# JacDacMicroBitShieldLP_29.net
KiCad netlist of a schematic drawn in Altium Designer
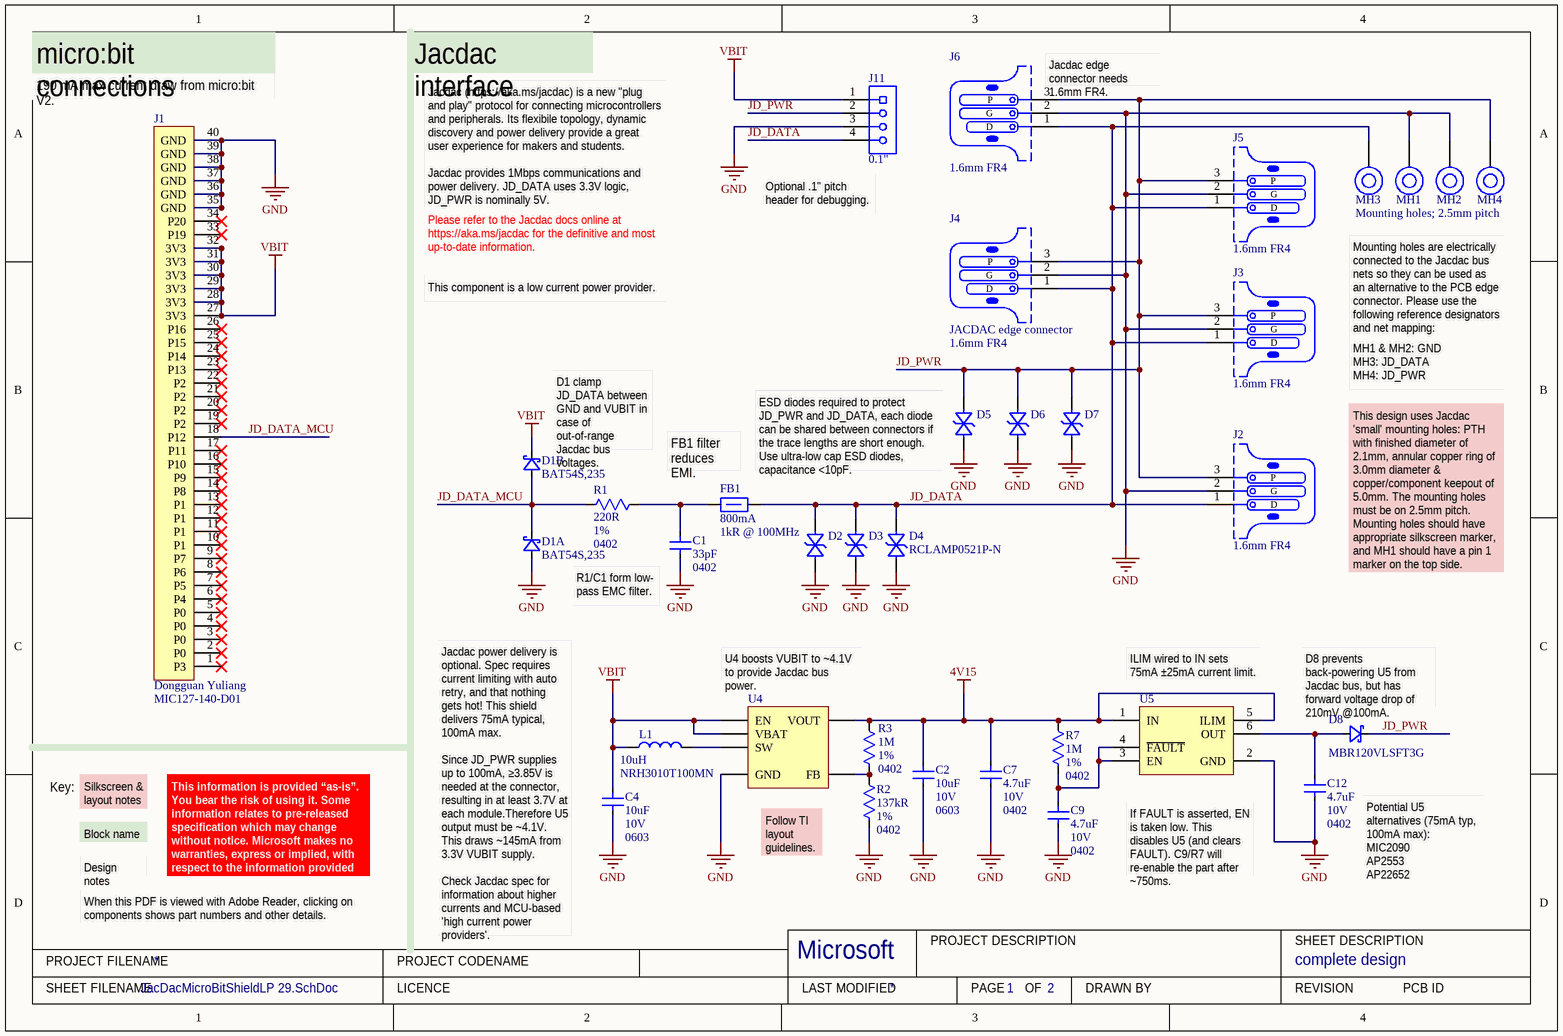
[diagram p0: JacDacMicroBitShieldLP 29.SchDoc]

(export (version "E")
  (design (tool "Eeschema 10.0.6"))
  (components
    (comp (ref "C1")
      (value "CL05C330JB51PNC")
      (footprint "C0402_0.55MM - without outline")
      (description "CAP CER 33PF 50V NP0 0402")
      (fields
        (field (name "MANUFACTURER") "Samsung")
        (field (name "TOLERANCE") "5%")
        (field (name "CAPACITANCE") "33pF")
        (field (name "CASE CODE (IMPERIAL)") "0402")
        (field (name "CHECKED") "?")
        (field (name "CREATED") "DG")
      )
      (libsource (lib "Samsung") (part "CL05C330JB51PNC"))
    )
    (comp (ref "C2")
      (value "CL10A106KP8NNNC")
      (footprint "C0603 - without outline")
      (description "CAP CER 10UF 10V X5R 0603")
      (fields
        (field (name "MANUFACTURER") "Samsung")
        (field (name "TOLERANCE") "10%")
        (field (name "CAPACITANCE") "10uF")
        (field (name "VOLTAGE RATING") "10V")
        (field (name "CASE CODE (IMPERIAL)") "0603")
      )
      (libsource (lib "Samsung") (part "CL10A106KP8NNNC"))
    )
    (comp (ref "C4")
      (value "CL10A106KP8NNNC")
      (footprint "C0603 - without outline")
      (description "CAP CER 10UF 10V X5R 0603")
      (fields
        (field (name "MANUFACTURER") "Samsung")
        (field (name "TOLERANCE") "10%")
        (field (name "CAPACITANCE") "10uF")
        (field (name "VOLTAGE RATING") "10V")
        (field (name "CASE CODE (IMPERIAL)") "0603")
      )
      (libsource (lib "Samsung") (part "CL10A106KP8NNNC"))
    )
    (comp (ref "C7")
      (value "CL05A475MP5NRNC")
      (footprint "R0402 - Without outline")
      (description "CAP CER 4.7UF 10V X5R 0402")
      (fields
        (field (name "MANUFACTURER") "Samsung")
        (field (name "TOLERANCE") "20%")
        (field (name "CAPACITANCE") "4.7uF")
        (field (name "VOLTAGE RATING") "10V")
        (field (name "CASE CODE (IMPERIAL)") "0402")
        (field (name "CREATED BY") "D. Gakure")
        (field (name "CHECKED BY") "?")
      )
      (libsource (lib "Samsung") (part "CL05A475MP5NRNC"))
    )
    (comp (ref "C9")
      (value "CL05A475MP5NRNC")
      (footprint "R0402 - Without outline")
      (description "CAP CER 4.7UF 10V X5R 0402")
      (fields
        (field (name "MANUFACTURER") "Samsung")
        (field (name "TOLERANCE") "20%")
        (field (name "CAPACITANCE") "4.7uF")
        (field (name "VOLTAGE RATING") "10V")
        (field (name "CASE CODE (IMPERIAL)") "0402")
        (field (name "CREATED BY") "D. Gakure")
        (field (name "CHECKED BY") "?")
      )
      (libsource (lib "Samsung") (part "CL05A475MP5NRNC"))
    )
    (comp (ref "C12")
      (value "CL05A475MP5NRNC")
      (footprint "R0402 - Without outline")
      (description "CAP CER 4.7UF 10V X5R 0402")
      (fields
        (field (name "MANUFACTURER") "Samsung")
        (field (name "TOLERANCE") "20%")
        (field (name "CAPACITANCE") "4.7uF")
        (field (name "VOLTAGE RATING") "10V")
        (field (name "CASE CODE (IMPERIAL)") "0402")
        (field (name "CREATED BY") "D. Gakure")
        (field (name "CHECKED BY") "?")
      )
      (libsource (lib "Samsung") (part "CL05A475MP5NRNC"))
    )
    (comp (ref "D1")
      (value "BAT54S")
      (footprint "NXP-BAT54S-TO-236AB - without outline")
      (description "DIODE ARRAY SCHOTTKY 30V SOT23")
      (fields (field (name "MANUFACTURER") "Nexperia") (field (name "MANUFACTURER PART NUMBER") "BAT54S,235"))
      (libsource (lib "NXP") (part "BAT54S"))
    )
    (comp (ref "D2")
      (value "RCLAMP0521P-N")
      (footprint "TVS 0402 - L")
      (description "Bidirectional 5V (Max) 6V 16V 3.5A (8/20us) 0402 TVS RoHS")
      (fields
        (field (name "MANUFACTURER") "Born Semiconductor")
        (field (name "CREATED BY") "D Gakure")
        (field (name "CHECKED BY") "?")
      )
      (libsource (lib "BornSemiconductor") (part "RCLAMP0521P-N"))
    )
    (comp (ref "D3")
      (value "RCLAMP0521P-N")
      (footprint "TVS 0402 - L")
      (description "Bidirectional 5V (Max) 6V 16V 3.5A (8/20us) 0402 TVS RoHS")
      (fields
        (field (name "MANUFACTURER") "Born Semiconductor")
        (field (name "CREATED BY") "D Gakure")
        (field (name "CHECKED BY") "?")
      )
      (libsource (lib "BornSemiconductor") (part "RCLAMP0521P-N"))
    )
    (comp (ref "D4")
      (value "RCLAMP0521P-N")
      (footprint "TVS 0402 - L")
      (description "Bidirectional 5V (Max) 6V 16V 3.5A (8/20us) 0402 TVS RoHS")
      (fields
        (field (name "MANUFACTURER") "Born Semiconductor")
        (field (name "MANUFACTURER PART NUMBER") "RCLAMP0521P-N")
        (field (name "CREATED BY") "D Gakure")
        (field (name "CHECKED BY") "?")
      )
      (libsource (lib "BornSemiconductor") (part "RCLAMP0521P-N"))
    )
    (comp (ref "D5")
      (value "RCLAMP0521P-N")
      (footprint "TVS 0402 - L")
      (description "Bidirectional 5V (Max) 6V 16V 3.5A (8/20us) 0402 TVS RoHS")
      (fields
        (field (name "MANUFACTURER") "Born Semiconductor")
        (field (name "CREATED BY") "D Gakure")
        (field (name "CHECKED BY") "?")
      )
      (libsource (lib "BornSemiconductor") (part "RCLAMP0521P-N"))
    )
    (comp (ref "D6")
      (value "RCLAMP0521P-N")
      (footprint "TVS 0402 - L")
      (description "Bidirectional 5V (Max) 6V 16V 3.5A (8/20us) 0402 TVS RoHS")
      (fields
        (field (name "MANUFACTURER") "Born Semiconductor")
        (field (name "CREATED BY") "D Gakure")
        (field (name "CHECKED BY") "?")
      )
      (libsource (lib "BornSemiconductor") (part "RCLAMP0521P-N"))
    )
    (comp (ref "D7")
      (value "RCLAMP0521P-N")
      (footprint "TVS 0402 - L")
      (description "Bidirectional 5V (Max) 6V 16V 3.5A (8/20us) 0402 TVS RoHS")
      (fields
        (field (name "MANUFACTURER") "Born Semiconductor")
        (field (name "CREATED BY") "D Gakure")
        (field (name "CHECKED BY") "?")
      )
      (libsource (lib "BornSemiconductor") (part "RCLAMP0521P-N"))
    )
    (comp (ref "D8")
      (value "MBR120VLSFT3G")
      (footprint "MBR120VLSFT3G")
      (description "DIODE SCHOTTKY 20V 1A SOD123FL")
      (fields
        (field (name "MANUFACTURER") "ON Semiconductor")
        (field (name "MANUFACTURER PART NUMBER") "MBR120VLSFT3G")
      )
      (libsource (lib "OnSemiconductor") (part "MBR120VLSFT3G"))
    )
    (comp (ref "FB1")
      (value "TDK MPZ1608S102ATA00")
      (footprint "TDK MPZ1608 0.8mm - without outline")
      (description "0603 1k@100MHz 0.8A chip")
      (fields
        (field (name "TOLERANCE") "25%")
        (field (name "MANUFACTURER") "TDK")
        (field (name "CURRENT RATING") "800mA")
        (field (name "IMPEDANCE") "1kR @ 100MHz")
      )
      (libsource (lib "TDK") (part "TDK MPZ1608S102ATA00"))
    )
    (comp (ref "J1")
      (value "Planar 1x40p 1.27 mm pitch edge connector for the micro:bit")
      (footprint "MIC127-140-D01")
      (description "\"Same plane\" 1x40p 1.27mm Dongguan Yuliang BBC micro:bit edge connector")
      (fields
        (field (name "MANUFACTURER") "Dongguan Yuliang")
        (field (name "MANUFACTURER PART NUMBER") "MIC127-140-D01")
      )
      (libsource (lib "Yuliang") (part "MIC127-140-D01"))
    )
    (comp (ref "J2")
      (value "Jacdac edge connector")
      (footprint "JACDAC_edge_connector:JACDAC_EDGE_CONNECTOR_NO_TRACES")
      (description "3 pin jacdac edge connector 1.27mm pitch")
      (fields
        (field (name "MANUFACTURER PART NUMBER") "JACDAC_EDGE_CONNECTOR")
        (field (name "PCB TYPE") "1.6mm FR4")
        (field (name "CHECKED BY") "?")
        (field (name "CREATED BY") "D. Gakure")
      )
      (libsource (lib "generic-con") (part "Jacdac edge connector"))
    )
    (comp (ref "J3")
      (value "Jacdac edge connector")
      (footprint "JACDAC_edge_connector:JACDAC_EDGE_CONNECTOR_NO_TRACES")
      (description "3 pin jacdac edge connector 1.27mm pitch")
      (fields
        (field (name "MANUFACTURER PART NUMBER") "JACDAC_EDGE_CONNECTOR")
        (field (name "PCB TYPE") "1.6mm FR4")
        (field (name "CHECKED BY") "?")
        (field (name "CREATED BY") "D. Gakure")
      )
      (libsource (lib "generic-con") (part "Jacdac edge connector"))
    )
    (comp (ref "J4")
      (value "JACDAC edge connector")
      (footprint "JACDAC_edge_connector:JACDAC_EDGE_CONNECTOR_NO_TRACES")
      (description "3 pin jacdac edge connector 1.27mm pitch")
      (fields
        (field (name "MANUFACTURER PART NUMBER") "JACDAC_EDGE_CONNECTOR")
        (field (name "PCB TYPE") "1.6mm FR4")
        (field (name "CHECKED BY") "?")
        (field (name "CREATED BY") "D. Gakure")
      )
      (libsource (lib "") (part "Jacdac edge connector_1"))
    )
    (comp (ref "J5")
      (value "Jacdac edge connector")
      (footprint "JACDAC_edge_connector:JACDAC_EDGE_CONNECTOR_NO_TRACES")
      (description "3 pin jacdac edge connector 1.27mm pitch")
      (fields
        (field (name "MANUFACTURER PART NUMBER") "JACDAC_EDGE_CONNECTOR")
        (field (name "PCB TYPE") "1.6mm FR4")
        (field (name "CHECKED BY") "?")
        (field (name "CREATED BY") "D. Gakure")
      )
      (libsource (lib "generic-con") (part "Jacdac edge connector"))
    )
    (comp (ref "J6")
      (value "Jacdac edge connector")
      (footprint "JACDAC_edge_connector:JACDAC_EDGE_CONNECTOR_NO_TRACES")
      (description "3 pin jacdac edge connector 1.27mm pitch")
      (fields
        (field (name "MANUFACTURER PART NUMBER") "JACDAC_EDGE_CONNECTOR")
        (field (name "PCB TYPE") "1.6mm FR4")
        (field (name "CHECKED BY") "?")
        (field (name "CREATED BY") "D. Gakure")
      )
      (libsource (lib "") (part "Jacdac edge connector_1"))
    )
    (comp (ref "J11")
      (value "0.1\"")
      (footprint "Generic 1x4 2.54mm header")
      (description "2.54mm, 4x1 way, vertical, square pin, gold plate")
      (fields
        (field (name "MANUFACTURER") "Multicomp")
        (field (name "MANUFACTURER PART NUMBER") "2211S-04G")
        (field (name "CREATED BY") "HUGHWI")
      )
      (libsource (lib "generic-con") (part "Header Multicomp 2211S-04G-whitesch"))
    )
    (comp (ref "L1")
      (value "NRH3010T100MN")
      (footprint "NRH3010T100MN")
      (fields
        (field (name "TOLERANCE") "20%")
        (field (name "INDUCTANCE") "10uH")
        (field (name "MANUFACTURER") "Taiyo Yuden")
        (field (name "MANUFACTURER PART NUMBER") "NRH3010T100MN")
      )
      (libsource (lib "TaiyoYuden ") (part "NRH3010T100MN"))
    )
    (comp (ref "MH1")
      (value "~")
      (footprint "MH_5.0MMK_3.0MMC_2.1MMD_PTH:MH_5.0MMK_3.0MMC_2.1MMD_PTH")
      (description "Mounting Hole 5.0mm keepout, 3.0mm annualar ring and 2.1mm Drill PTH")
      (libsource (lib "generic") (part "MH_5.0MMK_3.0MMC_2.1MMD_PTH"))
    )
    (comp (ref "MH2")
      (value "Mounting holes; 2.5 mm pitch")
      (footprint "MH_5.0MMK_3.0MMC_2.1MMD_PTH:MH_5.0MMK_3.0MMC_2.1MMD_PTH")
      (description "Mounting Hole 5.0mm keepout, 3.0mm annualar ring and 2.1mm Drill PTH")
      (libsource (lib "generic") (part "MH_5.0MMK_3.0MMC_2.1MMD_PTH"))
    )
    (comp (ref "MH3")
      (value "Mounting holes; 2.5mm pitch")
      (footprint "MH_5.0MMK_3.0MMC_2.1MMD_PTH:MH_5.0MMK_3.0MMC_2.1MMD_PTH")
      (description "Mounting Hole 5.0mm keepout, 3.0mm annualar ring and 2.1mm Drill PTH")
      (libsource (lib "generic") (part "MH_5.0MMK_3.0MMC_2.1MMD_PTH"))
    )
    (comp (ref "MH4")
      (value "MH_5.0MMK_3.0MMC_2.1MMD_PTH")
      (footprint "MH_5.0MMK_3.0MMC_2.1MMD_PTH:MH_5.0MMK_3.0MMC_2.1MMD_PTH")
      (description "Mounting Hole 5.0mm keepout, 3.0mm annualar ring and 2.1mm Drill PTH")
      (libsource (lib "generic") (part "MH_5.0MMK_3.0MMC_2.1MMD_PTH"))
    )
    (comp (ref "R1")
      (value "0402WGF2200TCE")
      (footprint "UNIROYAL-0402:R0402 - Without outline")
      (description "RES SMD 220 OHM 1% 1/16W 0402")
      (fields
        (field (name "MANUFACTURER") "Uniroyal Elec")
        (field (name "RESISTANCE") "220R")
        (field (name "TOLERANCE") "1%")
        (field (name "CASE CODE (IMPERIAL)") "0402")
      )
      (libsource (lib "UniroyalElec") (part "0402WGF2200TCE"))
    )
    (comp (ref "R2")
      (value "RC0402FR-07137KL")
      (footprint "R0402 - Without outline")
      (description "RES SMD 137K OHM 1% 1/16W 0402")
      (fields
        (field (name "MANUFACTURER") "Yageo")
        (field (name "RESISTANCE") "137kR")
        (field (name "TOLERANCE") "1%")
        (field (name "CASE CODE (IMPERIAL)") "0402")
      )
      (libsource (lib "Yageo") (part "RC0402FR-07137KL"))
    )
    (comp (ref "R3")
      (value "0402WGF1004TCE")
      (footprint "UNIROYAL-0402:R0402 - Without outline")
      (description "RES SMD 1M OHM 1% 1/16W 0402")
      (fields
        (field (name "MANUFACTURER") "Uniroyal Elec")
        (field (name "RESISTANCE") "1M")
        (field (name "TOLERANCE") "1%")
        (field (name "CASE CODE (IMPERIAL)") "0402")
      )
      (libsource (lib "UniroyalElec") (part "0402WGF1004TCE"))
    )
    (comp (ref "R7")
      (value "0402WGF1004TCE")
      (footprint "UNIROYAL-0402:R0402 - Without outline")
      (description "RES SMD 1M OHM 1% 1/16W 0402")
      (fields
        (field (name "MANUFACTURER") "Uniroyal Elec")
        (field (name "RESISTANCE") "1M")
        (field (name "TOLERANCE") "1%")
        (field (name "CASE CODE (IMPERIAL)") "0402")
      )
      (libsource (lib "UniroyalElec") (part "0402WGF1004TCE"))
    )
    (comp (ref "U4")
      (value "TLV61220")
      (footprint "TI-TLV61220 - without_outline")
      (description "IC REG BST ADJ 0.22A SYNC SOT23")
      (fields (field (name "MANUFACTURER PART NUMBER") "TLV61220DBVR"))
      (libsource (lib "TexasInstruments") (part "TLV61220"))
    )
    (comp (ref "U5")
      (value "TPS2553DBVR")
      (footprint "TI-TPS2553 - without_outline")
      (libsource (lib "TexasInstruments") (part "TPS2553DBVR"))
    )
  )
  (nets
    (net (code "1") (name "/JD_DATA") (class "Default")
      (node (ref "D2") (pin "1") (pinfunction "K_1") (pintype "passive"))
      (node (ref "D3") (pin "1") (pinfunction "K_1") (pintype "passive"))
      (node (ref "D4") (pin "1") (pinfunction "K_1") (pintype "passive"))
      (node (ref "FB1") (pin "1") (pinfunction "1_1") (pintype "passive"))
      (node (ref "J11") (pin "4") (pinfunction "4_4") (pintype "passive"))
      (node (ref "J2") (pin "1") (pinfunction "D_1") (pintype "passive"))
      (node (ref "J3") (pin "1") (pinfunction "D_1") (pintype "passive"))
      (node (ref "J4") (pin "1") (pinfunction "D_1") (pintype "passive"))
      (node (ref "J5") (pin "1") (pinfunction "D_1") (pintype "passive"))
      (node (ref "J6") (pin "1") (pinfunction "D_1") (pintype "passive"))
      (node (ref "MH3") (pin "1") (pinfunction "1_1") (pintype "passive"))
    )
    (net (code "2") (name "/JD_DATA_MCU") (class "Default")
      (node (ref "D1") (pin "3") (pinfunction "K_3") (pintype "passive"))
      (node (ref "J1") (pin "18") (pinfunction "P12_18") (pintype "passive"))
      (node (ref "R1") (pin "1") (pinfunction "1_1") (pintype "passive"))
    )
    (net (code "3") (name "/JD_PWR") (class "Default")
      (node (ref "D5") (pin "1") (pinfunction "K_1") (pintype "passive"))
      (node (ref "D6") (pin "1") (pinfunction "K_1") (pintype "passive"))
      (node (ref "D7") (pin "1") (pinfunction "K_1") (pintype "passive"))
      (node (ref "D8") (pin "1") (pinfunction "K_1") (pintype "passive"))
      (node (ref "J11") (pin "2") (pinfunction "2_2") (pintype "passive"))
      (node (ref "J2") (pin "3") (pinfunction "P_3") (pintype "passive"))
      (node (ref "J3") (pin "3") (pinfunction "P_3") (pintype "passive"))
      (node (ref "J4") (pin "3") (pinfunction "P_3") (pintype "passive"))
      (node (ref "J5") (pin "3") (pinfunction "P_3") (pintype "passive"))
      (node (ref "J6") (pin "3") (pinfunction "P_3") (pintype "passive"))
      (node (ref "MH4") (pin "1") (pinfunction "1_1") (pintype "passive"))
    )
    (net (code "4") (name "4V15") (class "Default")
      (node (ref "C2") (pin "2") (pinfunction "2_2") (pintype "passive"))
      (node (ref "C7") (pin "2") (pinfunction "2_2") (pintype "passive"))
      (node (ref "R3") (pin "2") (pinfunction "2_2") (pintype "passive"))
      (node (ref "R7") (pin "2") (pinfunction "2_2") (pintype "passive"))
      (node (ref "U4") (pin "5") (pinfunction "VOUT_5") (pintype "passive"))
      (node (ref "U5") (pin "1") (pinfunction "IN_1") (pintype "passive"))
      (node (ref "U5") (pin "5") (pinfunction "ILIM_5") (pintype "passive"))
    )
    (net (code "5") (name "GND") (class "Default")
      (node (ref "C1") (pin "1") (pinfunction "1_1") (pintype "passive"))
      (node (ref "C12") (pin "1") (pinfunction "1_1") (pintype "passive"))
      (node (ref "C2") (pin "1") (pinfunction "1_1") (pintype "passive"))
      (node (ref "C4") (pin "1") (pinfunction "1_1") (pintype "passive"))
      (node (ref "C7") (pin "1") (pinfunction "1_1") (pintype "passive"))
      (node (ref "C9") (pin "1") (pinfunction "1_1") (pintype "passive"))
      (node (ref "D1") (pin "1") (pinfunction "A_1") (pintype "passive"))
      (node (ref "D2") (pin "2") (pinfunction "A_2") (pintype "passive"))
      (node (ref "D3") (pin "2") (pinfunction "A_2") (pintype "passive"))
      (node (ref "D4") (pin "2") (pinfunction "A_2") (pintype "passive"))
      (node (ref "D5") (pin "2") (pinfunction "A_2") (pintype "passive"))
      (node (ref "D6") (pin "2") (pinfunction "A_2") (pintype "passive"))
      (node (ref "D7") (pin "2") (pinfunction "A_2") (pintype "passive"))
      (node (ref "J1") (pin "35") (pinfunction "GND_35") (pintype "passive"))
      (node (ref "J1") (pin "36") (pinfunction "GND_36") (pintype "passive"))
      (node (ref "J1") (pin "37") (pinfunction "GND_37") (pintype "passive"))
      (node (ref "J1") (pin "38") (pinfunction "GND_38") (pintype "passive"))
      (node (ref "J1") (pin "39") (pinfunction "GND_39") (pintype "passive"))
      (node (ref "J1") (pin "40") (pinfunction "GND_40") (pintype "passive"))
      (node (ref "J11") (pin "3") (pinfunction "3_3") (pintype "passive"))
      (node (ref "J2") (pin "2") (pinfunction "G_2") (pintype "passive"))
      (node (ref "J3") (pin "2") (pinfunction "G_2") (pintype "passive"))
      (node (ref "J4") (pin "2") (pinfunction "G_2") (pintype "passive"))
      (node (ref "J5") (pin "2") (pinfunction "G_2") (pintype "passive"))
      (node (ref "J6") (pin "2") (pinfunction "G_2") (pintype "passive"))
      (node (ref "MH1") (pin "1") (pinfunction "1_1") (pintype "passive"))
      (node (ref "MH2") (pin "1") (pinfunction "1_1") (pintype "passive"))
      (node (ref "R2") (pin "1") (pinfunction "1_1") (pintype "passive"))
      (node (ref "U4") (pin "2") (pinfunction "GND_2") (pintype "passive"))
      (node (ref "U5") (pin "2") (pinfunction "GND_2") (pintype "passive"))
    )
    (net (code "6") (name "Net-(C1-Pad2)") (class "Default")
      (node (ref "C1") (pin "2") (pinfunction "2_2") (pintype "passive"))
      (node (ref "FB1") (pin "2") (pinfunction "2_2") (pintype "passive"))
      (node (ref "R1") (pin "2") (pinfunction "2_2") (pintype "passive"))
    )
    (net (code "7") (name "Net-(D8-A)") (class "Default")
      (node (ref "C12") (pin "2") (pinfunction "2_2") (pintype "passive"))
      (node (ref "D8") (pin "2") (pinfunction "A_2") (pintype "passive"))
      (node (ref "U5") (pin "6") (pinfunction "OUT_6") (pintype "passive"))
    )
    (net (code "8") (name "Net-(U4-FB)") (class "Default")
      (node (ref "R2") (pin "2") (pinfunction "2_2") (pintype "passive"))
      (node (ref "R3") (pin "1") (pinfunction "1_1") (pintype "passive"))
      (node (ref "U4") (pin "4") (pinfunction "FB_4") (pintype "passive"))
    )
    (net (code "9") (name "Net-(U4-SW)") (class "Default")
      (node (ref "L1") (pin "2") (pinfunction "2_2") (pintype "passive"))
      (node (ref "U4") (pin "1") (pinfunction "SW_1") (pintype "passive"))
    )
    (net (code "10") (name "Net-(U5-EN)") (class "Default")
      (node (ref "C9") (pin "2") (pinfunction "2_2") (pintype "passive"))
      (node (ref "R7") (pin "1") (pinfunction "1_1") (pintype "passive"))
      (node (ref "U5") (pin "3") (pinfunction "EN_3") (pintype "passive"))
      (node (ref "U5") (pin "4") (pinfunction "~{FAULT}_4") (pintype "passive"))
    )
    (net (code "11") (name "VBIT") (class "Default")
      (node (ref "C4") (pin "2") (pinfunction "2_2") (pintype "passive"))
      (node (ref "D1") (pin "2") (pinfunction "K_2") (pintype "passive"))
      (node (ref "J1") (pin "27") (pinfunction "3V3_27") (pintype "passive"))
      (node (ref "J1") (pin "28") (pinfunction "3V3_28") (pintype "passive"))
      (node (ref "J1") (pin "29") (pinfunction "3V3_29") (pintype "passive"))
      (node (ref "J1") (pin "30") (pinfunction "3V3_30") (pintype "passive"))
      (node (ref "J1") (pin "31") (pinfunction "3V3_31") (pintype "passive"))
      (node (ref "J1") (pin "32") (pinfunction "3V3_32") (pintype "passive"))
      (node (ref "J11") (pin "1") (pinfunction "1_1") (pintype "passive"))
      (node (ref "L1") (pin "1") (pinfunction "1_1") (pintype "passive"))
      (node (ref "U4") (pin "3") (pinfunction "EN_3") (pintype "passive"))
      (node (ref "U4") (pin "6") (pinfunction "VBAT_6") (pintype "passive"))
    )
    (net (code "12") (name "unconnected-(J1-P0-Pad2)") (class "Default")
      (node (ref "J1") (pin "2") (pinfunction "P0_2") (pintype "passive+no_connect"))
    )
    (net (code "13") (name "unconnected-(J1-P0-Pad3)") (class "Default")
      (node (ref "J1") (pin "3") (pinfunction "P0_3") (pintype "passive+no_connect"))
    )
    (net (code "14") (name "unconnected-(J1-P0-Pad4)") (class "Default")
      (node (ref "J1") (pin "4") (pinfunction "P0_4") (pintype "passive+no_connect"))
    )
    (net (code "15") (name "unconnected-(J1-P0-Pad5)") (class "Default")
      (node (ref "J1") (pin "5") (pinfunction "P0_5") (pintype "passive+no_connect"))
    )
    (net (code "16") (name "unconnected-(J1-P1-Pad10)") (class "Default")
      (node (ref "J1") (pin "10") (pinfunction "P1_10") (pintype "passive+no_connect"))
    )
    (net (code "17") (name "unconnected-(J1-P1-Pad11)") (class "Default")
      (node (ref "J1") (pin "11") (pinfunction "P1_11") (pintype "passive+no_connect"))
    )
    (net (code "18") (name "unconnected-(J1-P1-Pad12)") (class "Default")
      (node (ref "J1") (pin "12") (pinfunction "P1_12") (pintype "passive+no_connect"))
    )
    (net (code "19") (name "unconnected-(J1-P1-Pad13)") (class "Default")
      (node (ref "J1") (pin "13") (pinfunction "P1_13") (pintype "passive+no_connect"))
    )
    (net (code "20") (name "unconnected-(J1-P2-Pad19)") (class "Default")
      (node (ref "J1") (pin "19") (pinfunction "P2_19") (pintype "passive+no_connect"))
    )
    (net (code "21") (name "unconnected-(J1-P2-Pad20)") (class "Default")
      (node (ref "J1") (pin "20") (pinfunction "P2_20") (pintype "passive+no_connect"))
    )
    (net (code "22") (name "unconnected-(J1-P2-Pad21)") (class "Default")
      (node (ref "J1") (pin "21") (pinfunction "P2_21") (pintype "passive+no_connect"))
    )
    (net (code "23") (name "unconnected-(J1-P2-Pad22)") (class "Default")
      (node (ref "J1") (pin "22") (pinfunction "P2_22") (pintype "passive+no_connect"))
    )
    (net (code "24") (name "unconnected-(J1-P3-Pad1)") (class "Default")
      (node (ref "J1") (pin "1") (pinfunction "P3_1") (pintype "passive+no_connect"))
    )
    (net (code "25") (name "unconnected-(J1-P4-Pad6)") (class "Default")
      (node (ref "J1") (pin "6") (pinfunction "P4_6") (pintype "passive+no_connect"))
    )
    (net (code "26") (name "unconnected-(J1-P5-Pad7)") (class "Default")
      (node (ref "J1") (pin "7") (pinfunction "P5_7") (pintype "passive+no_connect"))
    )
    (net (code "27") (name "unconnected-(J1-P6-Pad8)") (class "Default")
      (node (ref "J1") (pin "8") (pinfunction "P6_8") (pintype "passive+no_connect"))
    )
    (net (code "28") (name "unconnected-(J1-P7-Pad9)") (class "Default")
      (node (ref "J1") (pin "9") (pinfunction "P7_9") (pintype "passive+no_connect"))
    )
    (net (code "29") (name "unconnected-(J1-P8-Pad14)") (class "Default")
      (node (ref "J1") (pin "14") (pinfunction "P8_14") (pintype "passive+no_connect"))
    )
    (net (code "30") (name "unconnected-(J1-P9-Pad15)") (class "Default")
      (node (ref "J1") (pin "15") (pinfunction "P9_15") (pintype "passive+no_connect"))
    )
    (net (code "31") (name "unconnected-(J1-P10-Pad16)") (class "Default")
      (node (ref "J1") (pin "16") (pinfunction "P10_16") (pintype "passive+no_connect"))
    )
    (net (code "32") (name "unconnected-(J1-P11-Pad17)") (class "Default")
      (node (ref "J1") (pin "17") (pinfunction "P11_17") (pintype "passive+no_connect"))
    )
    (net (code "33") (name "unconnected-(J1-P13-Pad23)") (class "Default")
      (node (ref "J1") (pin "23") (pinfunction "P13_23") (pintype "passive+no_connect"))
    )
    (net (code "34") (name "unconnected-(J1-P14-Pad24)") (class "Default")
      (node (ref "J1") (pin "24") (pinfunction "P14_24") (pintype "passive+no_connect"))
    )
    (net (code "35") (name "unconnected-(J1-P15-Pad25)") (class "Default")
      (node (ref "J1") (pin "25") (pinfunction "P15_25") (pintype "passive+no_connect"))
    )
    (net (code "36") (name "unconnected-(J1-P16-Pad26)") (class "Default")
      (node (ref "J1") (pin "26") (pinfunction "P16_26") (pintype "passive+no_connect"))
    )
    (net (code "37") (name "unconnected-(J1-P19-Pad33)") (class "Default")
      (node (ref "J1") (pin "33") (pinfunction "P19_33") (pintype "passive+no_connect"))
    )
    (net (code "38") (name "unconnected-(J1-P20-Pad34)") (class "Default")
      (node (ref "J1") (pin "34") (pinfunction "P20_34") (pintype "passive+no_connect"))
    )
  )
)
